# Mobile_device_sheet3_pin_map.net
KiCad netlist of a schematic drawn in Altium Designer
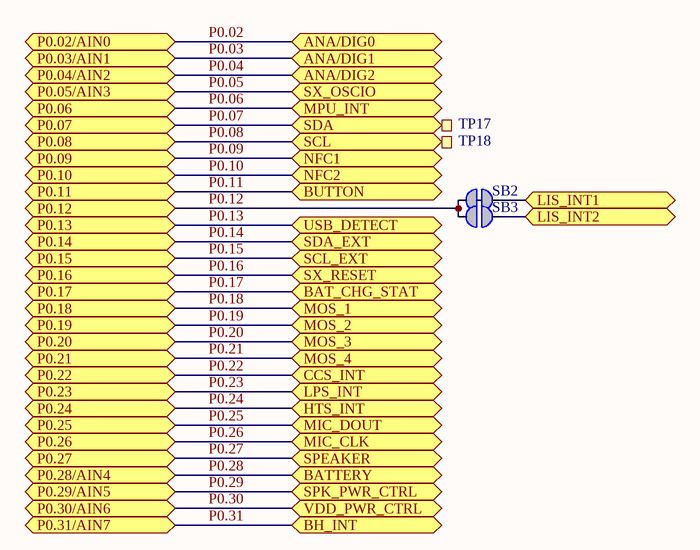
[diagram p0: Mobile_device_sheet3_pin_map.SchDoc]

(export (version "E")
  (design (tool "Eeschema 10.0.6"))
  (components
    (comp (ref "SB2")
      (value "Solderbridge")
      (footprint "Solderbridge_Shorted")
      (description "Shorted Solderbridge")
      (fields
        (field (name "PART NUMBER") "Solderbridge Shorted")
        (field (name "PUBLISHER") "Nordic Semiconductor")
      )
      (libsource (lib "Nordic Passive DB") (part "SOLDERBRIDGE_SHORTED"))
    )
    (comp (ref "SB3")
      (value "Solderbridge")
      (footprint "Solderbridge")
      (fields (field (name "PUBLISHER") "Nordic Semiconductor"))
      (libsource (lib "Nordic Passive DB") (part "SOLDERBRIDGE"))
    )
    (comp (ref "TP17")
      (value "Ø1.5mm,SMD")
      (footprint "TP_SMD_Ø1.5mm")
      (description "1.0mm circular SMD testpad")
      (fields
        (field (name "PART NUMBER") "TP_SMD_Ø1.5MM")
        (field (name "MANUFACTURER") "Nordic Semiconductor")
        (field (name "PUBLISHER") "Nordic Semiconductor")
      )
      (libsource (lib "Nordic Passive DB") (part "TESTPAD"))
    )
    (comp (ref "TP18")
      (value "Ø1.5mm,SMD")
      (footprint "TP_SMD_Ø1.5mm")
      (description "1.0mm circular SMD testpad")
      (fields
        (field (name "PART NUMBER") "TP_SMD_Ø1.5MM")
        (field (name "MANUFACTURER") "Nordic Semiconductor")
        (field (name "PUBLISHER") "Nordic Semiconductor")
      )
      (libsource (lib "Nordic Passive DB") (part "TESTPAD"))
    )
  )
  (nets
    (net (code "1") (name "/LIS_INT1") (class "Default")
      (node (ref "SB2") (pin "1") (pinfunction "0_1") (pintype "passive"))
    )
    (net (code "2") (name "/LIS_INT2") (class "Default")
      (node (ref "SB3") (pin "1") (pinfunction "0_1") (pintype "passive"))
    )
    (net (code "8") (name "/P0.07") (class "Default")
      (node (ref "TP17") (pin "1") (pinfunction "1_1") (pintype "passive"))
    )
    (net (code "9") (name "/P0.08") (class "Default")
      (node (ref "TP18") (pin "1") (pinfunction "1_1") (pintype "passive"))
    )
    (net (code "13") (name "/P0.12") (class "Default")
      (node (ref "SB2") (pin "2") (pinfunction "1_2") (pintype "passive"))
      (node (ref "SB3") (pin "2") (pinfunction "1_2") (pintype "passive"))
    )
  )
)
